# copycat_switch.net
KiCad netlist of a schematic drawn in EAGLE
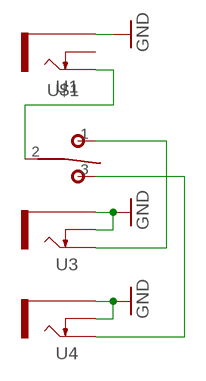
[diagram p0: schematic, sheet 1]

(export (version "E")
  (design (tool "Eeschema 10.0.6"))
  (components
    (comp (ref "U$1")
      (value "T-80-T-SPDT-ON-OFF-ON")
      (footprint "eagle-import:M9040P")
      (libsource (lib "eagle-import") (part "T-80-T-SPDT-ON-OFF-ON"))
    )
    (comp (ref "U1")
      (value "THONKICONNNEW")
      (footprint "eagle-import:WQP-PJ301M-12_JACK")
      (libsource (lib "eagle-import") (part "THONKICONNNEW"))
    )
    (comp (ref "U3")
      (value "THONKICONNNEW")
      (footprint "eagle-import:WQP-PJ301M-12_JACK")
      (libsource (lib "eagle-import") (part "THONKICONNNEW"))
    )
    (comp (ref "U4")
      (value "THONKICONNNEW")
      (footprint "eagle-import:WQP-PJ301M-12_JACK")
      (libsource (lib "eagle-import") (part "THONKICONNNEW"))
    )
  )
  (nets
    (net (code "1") (name "GND") (class "Default")
      (node (ref "U1") (pin "P$3_SLEEVE") (pinfunction "SLEEVE_P$3_SLEEVE") (pintype "passive"))
      (node (ref "U3") (pin "P$2_SWITCH") (pinfunction "SWITCH_P$2_SWITCH") (pintype "passive"))
      (node (ref "U3") (pin "P$3_SLEEVE") (pinfunction "SLEEVE_P$3_SLEEVE") (pintype "passive"))
      (node (ref "U4") (pin "P$2_SWITCH") (pinfunction "SWITCH_P$2_SWITCH") (pintype "passive"))
      (node (ref "U4") (pin "P$3_SLEEVE") (pinfunction "SLEEVE_P$3_SLEEVE") (pintype "passive"))
    )
    (net (code "2") (name "Net-(U$1-O)") (class "Default")
      (node (ref "U$1") (pin "1") (pinfunction "O_1") (pintype "passive"))
      (node (ref "U3") (pin "P$1_TIP") (pinfunction "TIP_P$1_TIP") (pintype "passive"))
    )
    (net (code "3") (name "Net-(U$1-P)") (class "Default")
      (node (ref "U$1") (pin "2") (pinfunction "P_2") (pintype "passive"))
      (node (ref "U1") (pin "P$1_TIP") (pinfunction "TIP_P$1_TIP") (pintype "passive"))
    )
    (net (code "4") (name "Net-(U$1-S)") (class "Default")
      (node (ref "U$1") (pin "3") (pinfunction "S_3") (pintype "passive"))
      (node (ref "U4") (pin "P$1_TIP") (pinfunction "TIP_P$1_TIP") (pintype "passive"))
    )
    (net (code "5") (name "unconnected-(U1-SWITCH-PadP$2_SWITCH)") (class "Default")
      (node (ref "U1") (pin "P$2_SWITCH") (pinfunction "SWITCH_P$2_SWITCH") (pintype "passive"))
    )
  )
)
